# EEZ_DIB_AUX_PS_r2B1.net
KiCad netlist of a schematic drawn in EAGLE
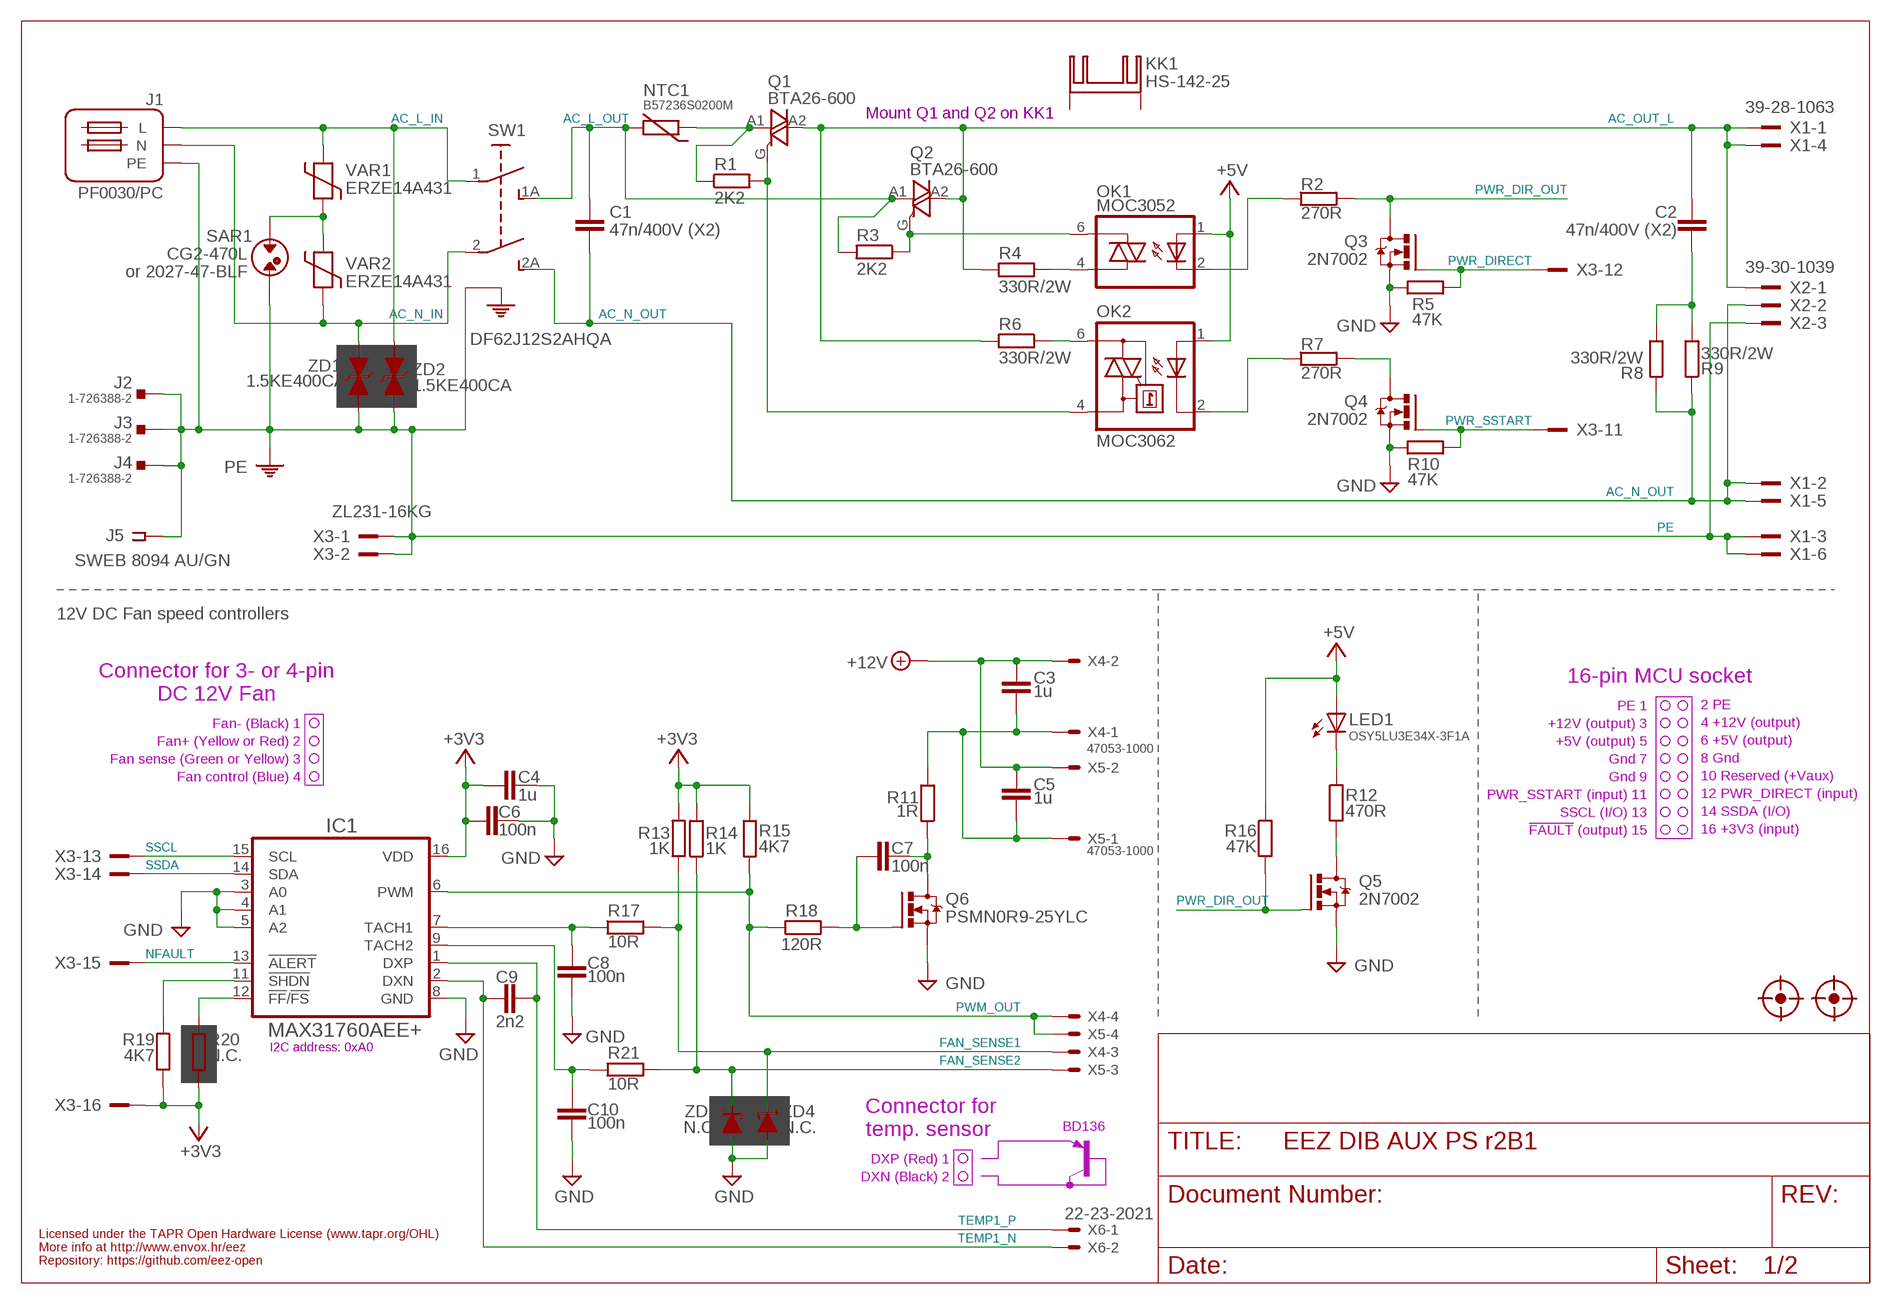
[diagram p0: schematic, sheet 1]
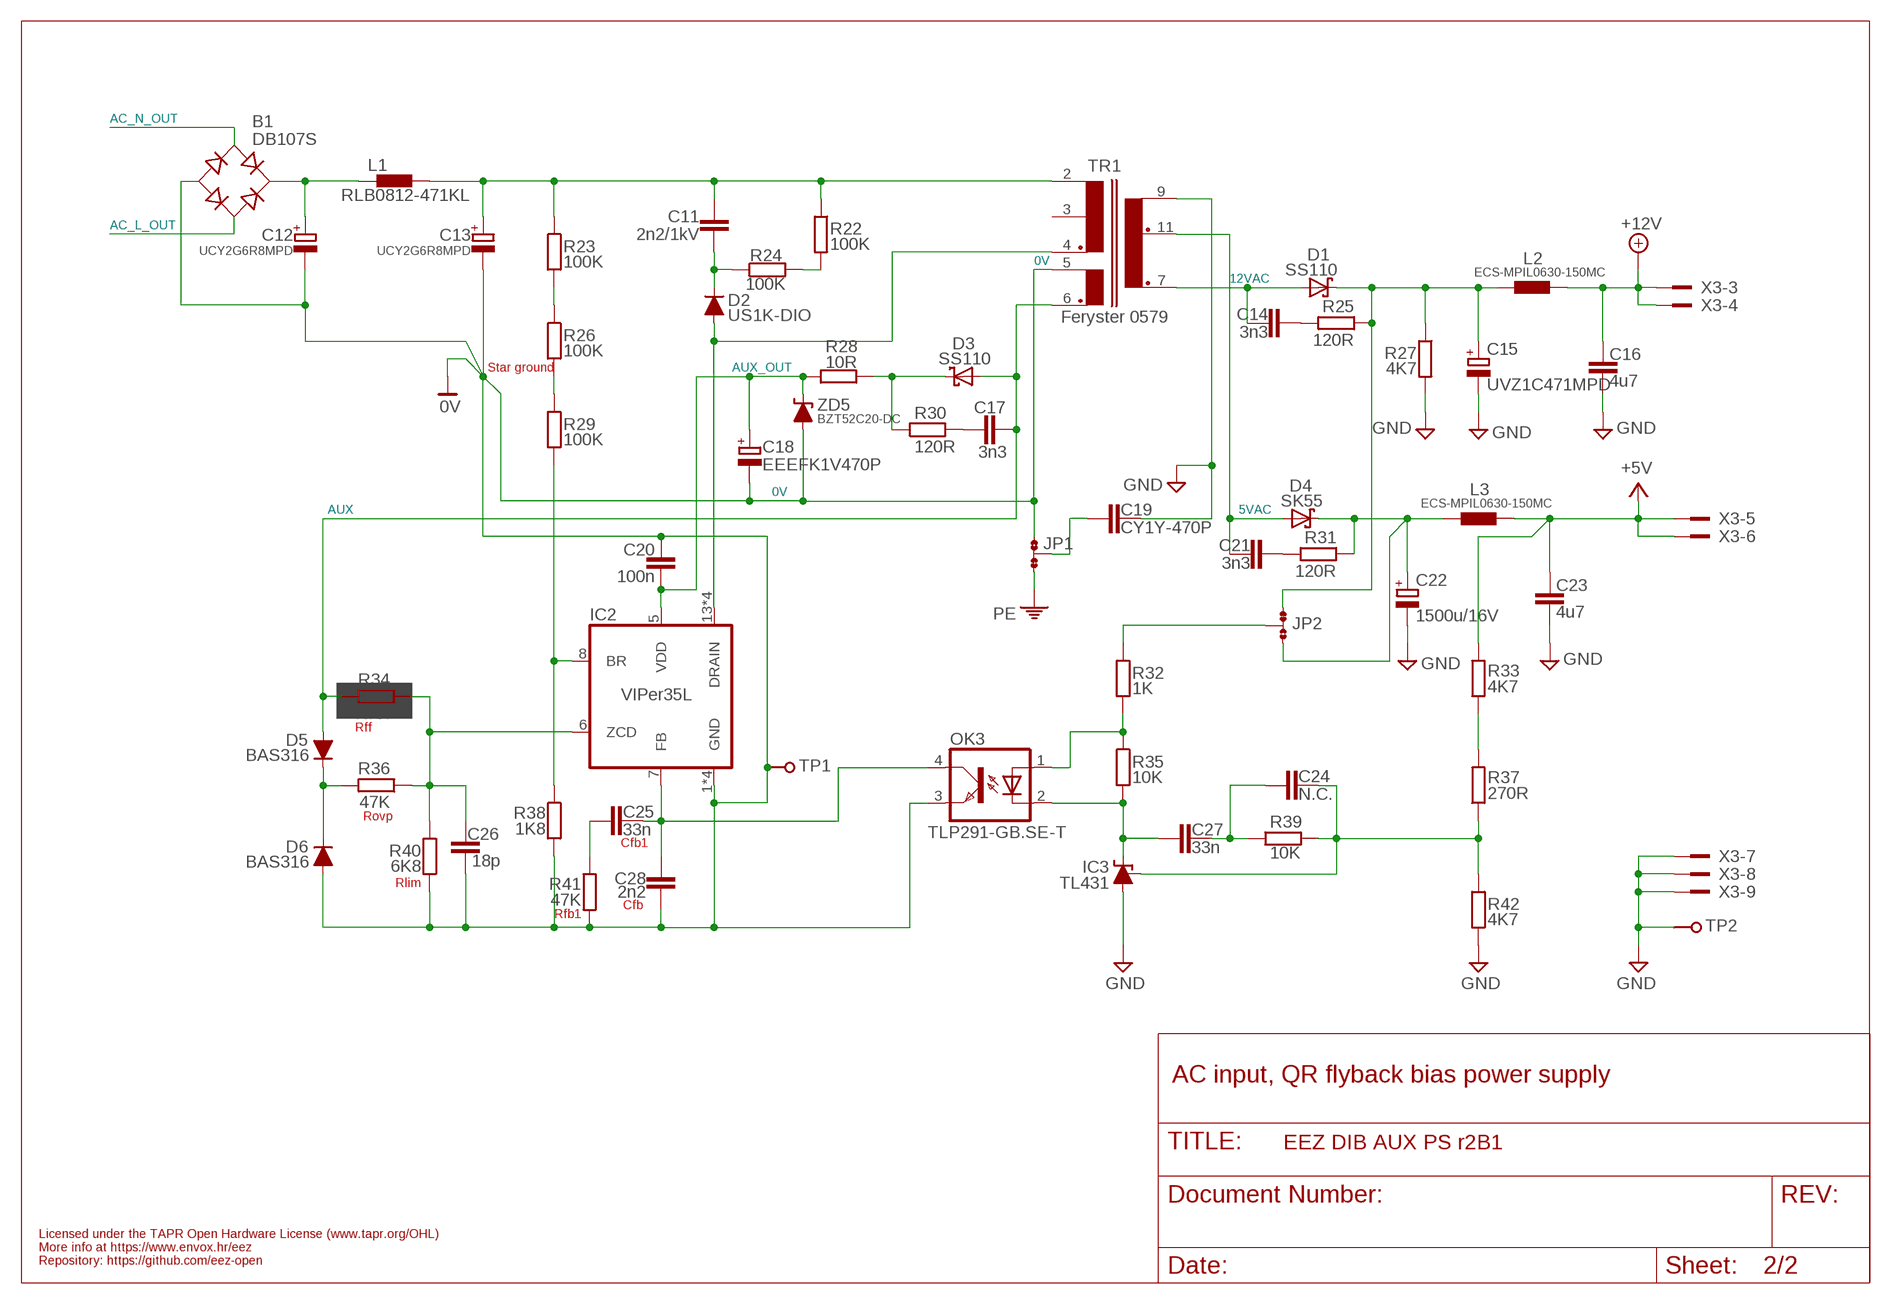
[diagram p1: schematic, sheet 2]

(export (version "E")
  (design (tool "Eeschema 10.0.6"))
  (components
    (comp (ref "B1")
      (value "DB107S")
      (footprint "eagle-import:DBS")
      (libsource (lib "eagle-import") (part "DB?GS107"))
    )
    (comp (ref "C11")
      (value "2n2/1kV")
      (footprint "eagle-import:C1210")
      (libsource (lib "eagle-import") (part "C-EUC1210"))
    )
    (comp (ref "C12")
      (value "UCY2G6R8MPD")
      (footprint "eagle-import:ECAP5_10.5")
      (libsource (lib "eagle-import") (part "ECAP5G_10.5MM"))
    )
    (comp (ref "C13")
      (value "UCY2G6R8MPD")
      (footprint "eagle-import:ECAP5_10.5")
      (libsource (lib "eagle-import") (part "ECAP5G_10.5MM"))
    )
    (comp (ref "C14")
      (value "3n3")
      (footprint "eagle-import:C0805")
      (libsource (lib "eagle-import") (part "C-EUC0805"))
    )
    (comp (ref "C15")
      (value "UVZ1C471MPD")
      (footprint "eagle-import:ECAP3.5_8")
      (libsource (lib "eagle-import") (part "ECAP3.5G_8MM"))
    )
    (comp (ref "C16")
      (value "4u7")
      (footprint "eagle-import:C1210")
      (libsource (lib "eagle-import") (part "C-EUC1210"))
    )
    (comp (ref "C17")
      (value "3n3")
      (footprint "eagle-import:C0805")
      (libsource (lib "eagle-import") (part "C-EUC0805"))
    )
    (comp (ref "C18")
      (value "EEEFK1V470P")
      (footprint "eagle-import:CAPAE660X610N")
      (libsource (lib "eagle-import") (part "ECAPPANASONIC_H"))
    )
    (comp (ref "C19")
      (value "CY1Y-470P")
      (footprint "eagle-import:CY075-032X103")
      (libsource (lib "eagle-import") (part "C-EUCY"))
    )
    (comp (ref "C20")
      (value "100n")
      (footprint "eagle-import:C0603")
      (libsource (lib "eagle-import") (part "C-EUC0603"))
    )
    (comp (ref "C21")
      (value "3n3")
      (footprint "eagle-import:C0805")
      (libsource (lib "eagle-import") (part "C-EUC0805"))
    )
    (comp (ref "C22")
      (value "1500u/16V")
      (footprint "eagle-import:ECAP5_13")
      (libsource (lib "eagle-import") (part "ECAP5G_13MM"))
    )
    (comp (ref "C23")
      (value "4u7")
      (footprint "eagle-import:C1210")
      (libsource (lib "eagle-import") (part "C-EUC1210"))
    )
    (comp (ref "C24")
      (value "N.C.")
      (footprint "eagle-import:C0805")
      (libsource (lib "eagle-import") (part "C-EUC0805"))
    )
    (comp (ref "C25")
      (value "33n")
      (footprint "eagle-import:C0805")
      (libsource (lib "eagle-import") (part "C-EUC0805"))
    )
    (comp (ref "C26")
      (value "18p")
      (footprint "eagle-import:C0603")
      (libsource (lib "eagle-import") (part "C-EUC0603"))
    )
    (comp (ref "C27")
      (value "33n")
      (footprint "eagle-import:C0805")
      (libsource (lib "eagle-import") (part "C-EUC0805"))
    )
    (comp (ref "C28")
      (value "2n2")
      (footprint "eagle-import:C0805")
      (libsource (lib "eagle-import") (part "C-EUC0805"))
    )
    (comp (ref "D1")
      (value "SS110")
      (footprint "eagle-import:SMB")
      (libsource (lib "eagle-import") (part "SCHOTTKYSMB"))
    )
    (comp (ref "D2")
      (value "US1K-DIO")
      (footprint "eagle-import:DO214AA")
      (libsource (lib "eagle-import") (part "DIODEDO214AA"))
    )
    (comp (ref "D3")
      (value "SS110")
      (footprint "eagle-import:SMB")
      (libsource (lib "eagle-import") (part "SCHOTTKYSMB"))
    )
    (comp (ref "D4")
      (value "SK55")
      (footprint "eagle-import:SMB")
      (libsource (lib "eagle-import") (part "SCHOTTKYSMB"))
    )
    (comp (ref "D5")
      (value "BAS316")
      (footprint "eagle-import:SOD323-R")
      (libsource (lib "eagle-import") (part "DIODESOD323R"))
    )
    (comp (ref "D6")
      (value "BAS316")
      (footprint "eagle-import:SOD323-R")
      (libsource (lib "eagle-import") (part "DIODESOD323R"))
    )
    (comp (ref "IC2")
      (value "VIPer35L")
      (footprint "eagle-import:SOIC-16")
      (libsource (lib "eagle-import") (part "VIPER35"))
    )
    (comp (ref "IC3")
      (value "TL431")
      (footprint "eagle-import:SOT103P240X110-3N")
      (libsource (lib "eagle-import") (part "TL431"))
    )
    (comp (ref "JP1")
      (value "JP3-CUT")
      (footprint "eagle-import:JP3-CUT")
      (libsource (lib "eagle-import") (part "JP3-CUT"))
    )
    (comp (ref "JP2")
      (value "JP3-CUT")
      (footprint "eagle-import:JP3-CUT")
      (libsource (lib "eagle-import") (part "JP3-CUT"))
    )
    (comp (ref "L1")
      (value "RLB0812-471KL")
      (footprint "eagle-import:FERSYTER_DSZ6")
      (libsource (lib "eagle-import") (part "FERYSTER_DSZ6"))
    )
    (comp (ref "L2")
      (value "ECS-MPIL0630-150MC")
      (footprint "eagle-import:DE0704")
      (libsource (lib "eagle-import") (part "DE0704"))
    )
    (comp (ref "L3")
      (value "ECS-MPIL0630-150MC")
      (footprint "eagle-import:DE0704")
      (libsource (lib "eagle-import") (part "DE0704"))
    )
    (comp (ref "OK3")
      (value "TLP291-GB.SE-T")
      (footprint "eagle-import:SO4")
      (libsource (lib "eagle-import") (part "TLP291"))
    )
    (comp (ref "R22")
      (value "100K")
      (footprint "eagle-import:R1206")
      (libsource (lib "eagle-import") (part "R-EU_R1206"))
    )
    (comp (ref "R23")
      (value "100K")
      (footprint "eagle-import:R1206")
      (libsource (lib "eagle-import") (part "R-EU_R1206"))
    )
    (comp (ref "R24")
      (value "100K")
      (footprint "eagle-import:R1206")
      (libsource (lib "eagle-import") (part "R-EU_R1206"))
    )
    (comp (ref "R25")
      (value "120R")
      (footprint "eagle-import:R0805")
      (libsource (lib "eagle-import") (part "R-EU_R0805"))
    )
    (comp (ref "R26")
      (value "100K")
      (footprint "eagle-import:R1206")
      (libsource (lib "eagle-import") (part "R-EU_R1206"))
    )
    (comp (ref "R27")
      (value "4K7")
      (footprint "eagle-import:R0805")
      (libsource (lib "eagle-import") (part "R-EU_R0805"))
    )
    (comp (ref "R28")
      (value "10R")
      (footprint "eagle-import:R0805")
      (libsource (lib "eagle-import") (part "R-EU_R0805"))
    )
    (comp (ref "R29")
      (value "100K")
      (footprint "eagle-import:R1206")
      (libsource (lib "eagle-import") (part "R-EU_R1206"))
    )
    (comp (ref "R30")
      (value "120R")
      (footprint "eagle-import:R0805")
      (libsource (lib "eagle-import") (part "R-EU_R0805"))
    )
    (comp (ref "R31")
      (value "120R")
      (footprint "eagle-import:R0805")
      (libsource (lib "eagle-import") (part "R-EU_R0805"))
    )
    (comp (ref "R32")
      (value "1K")
      (footprint "eagle-import:R0805")
      (libsource (lib "eagle-import") (part "R-EU_R0805"))
    )
    (comp (ref "R33")
      (value "4K7")
      (footprint "eagle-import:R0805")
      (libsource (lib "eagle-import") (part "R-EU_R0805"))
    )
    (comp (ref "R34")
      (value "N.C.")
      (footprint "eagle-import:R0805")
      (libsource (lib "eagle-import") (part "R-EU_R0805"))
    )
    (comp (ref "R35")
      (value "10K")
      (footprint "eagle-import:R0805")
      (libsource (lib "eagle-import") (part "R-EU_R0805"))
    )
    (comp (ref "R36")
      (value "47K")
      (footprint "eagle-import:R0805")
      (libsource (lib "eagle-import") (part "R-EU_R0805"))
    )
    (comp (ref "R37")
      (value "270R")
      (footprint "eagle-import:R0805")
      (libsource (lib "eagle-import") (part "R-EU_R0805"))
    )
    (comp (ref "R38")
      (value "1K8")
      (footprint "eagle-import:R0805")
      (libsource (lib "eagle-import") (part "R-EU_R0805"))
    )
    (comp (ref "R39")
      (value "10K")
      (footprint "eagle-import:R0805")
      (libsource (lib "eagle-import") (part "R-EU_R0805"))
    )
    (comp (ref "R40")
      (value "6K8")
      (footprint "eagle-import:R0805")
      (libsource (lib "eagle-import") (part "R-EU_R0805"))
    )
    (comp (ref "R41")
      (value "47K")
      (footprint "eagle-import:R0805")
      (libsource (lib "eagle-import") (part "R-EU_R0805"))
    )
    (comp (ref "R42")
      (value "4K7")
      (footprint "eagle-import:R0805")
      (libsource (lib "eagle-import") (part "R-EU_R0805"))
    )
    (comp (ref "TP1")
      (value "PCB_TEST_TABSHIELD")
      (footprint "eagle-import:PCB_SHIELD_TAB")
      (libsource (lib "eagle-import") (part "PCB_TEST_TABSHIELD"))
    )
    (comp (ref "TP2")
      (value "PCB_TEST_TABSHIELD")
      (footprint "eagle-import:PCB_SHIELD_TAB")
      (libsource (lib "eagle-import") (part "PCB_TEST_TABSHIELD"))
    )
    (comp (ref "TR1")
      (value "Feryster 0579")
      (footprint "eagle-import:FERYSTER_0579")
      (libsource (lib "eagle-import") (part "FERYSTER_0579"))
    )
    (comp (ref "X3")
      (value "ZL231-16KG")
      (footprint "eagle-import:ML16L")
      (libsource (lib "eagle-import") (part "IDC-16PIN-ANGLED"))
    )
    (comp (ref "ZD5")
      (value "BZT52C20-DC")
      (footprint "eagle-import:SOD123")
      (libsource (lib "eagle-import") (part "ZENER-DIODESOD123"))
    )
    (comp (ref "C1")
      (value "47n/400V (X2)")
      (footprint "eagle-import:C102-054X133")
      (libsource (lib "eagle-import") (part "C-EU102-054X133"))
    )
    (comp (ref "C2")
      (value "47n/400V (X2)")
      (footprint "eagle-import:C102-054X133")
      (libsource (lib "eagle-import") (part "C-EU102-054X133"))
    )
    (comp (ref "C3")
      (value "1u")
      (footprint "eagle-import:C0805")
      (libsource (lib "eagle-import") (part "C-EUC0805"))
    )
    (comp (ref "C4")
      (value "1u")
      (footprint "eagle-import:C0805")
      (libsource (lib "eagle-import") (part "C-EUC0805"))
    )
    (comp (ref "C5")
      (value "1u")
      (footprint "eagle-import:C0805")
      (libsource (lib "eagle-import") (part "C-EUC0805"))
    )
    (comp (ref "C6")
      (value "100n")
      (footprint "eagle-import:C0603")
      (libsource (lib "eagle-import") (part "C-EUC0603"))
    )
    (comp (ref "C7")
      (value "100n")
      (footprint "eagle-import:C0805")
      (libsource (lib "eagle-import") (part "C-EUC0805"))
    )
    (comp (ref "C8")
      (value "100n")
      (footprint "eagle-import:C0603")
      (libsource (lib "eagle-import") (part "C-EUC0603"))
    )
    (comp (ref "C9")
      (value "2n2")
      (footprint "eagle-import:C0805")
      (libsource (lib "eagle-import") (part "C-EUC0805"))
    )
    (comp (ref "C10")
      (value "100n")
      (footprint "eagle-import:C0603")
      (libsource (lib "eagle-import") (part "C-EUC0603"))
    )
    (comp (ref "FM1")
      (value "FIDUCIAL")
      (footprint "eagle-import:FIDUCIAL")
      (libsource (lib "eagle-import") (part "FIDUCIAL"))
    )
    (comp (ref "FM2")
      (value "FIDUCIAL")
      (footprint "eagle-import:FIDUCIAL")
      (libsource (lib "eagle-import") (part "FIDUCIAL"))
    )
    (comp (ref "IC1")
      (value "MAX31760AEE+")
      (footprint "eagle-import:DBQ16")
      (libsource (lib "eagle-import") (part "MAX31760AEE+"))
    )
    (comp (ref "J1")
      (value "PF0030/PC")
      (footprint "eagle-import:PF0030_PC")
      (libsource (lib "eagle-import") (part "PF0030/PC"))
    )
    (comp (ref "J2")
      (value "1-726388-2")
      (footprint "eagle-import:PCB_TAB-4.8MM")
      (libsource (lib "eagle-import") (part "PCB_TAB4.8MM"))
    )
    (comp (ref "J3")
      (value "1-726388-2")
      (footprint "eagle-import:PCB_TAB-4.8MM")
      (libsource (lib "eagle-import") (part "PCB_TAB4.8MM"))
    )
    (comp (ref "J4")
      (value "1-726388-2")
      (footprint "eagle-import:PCB_TAB-4.8MM")
      (libsource (lib "eagle-import") (part "PCB_TAB4.8MM"))
    )
    (comp (ref "J5")
      (value "SWEB 8094 AU/GN")
      (footprint "eagle-import:S16N-PC")
      (libsource (lib "eagle-import") (part "BINDING_POSTCLIFF"))
    )
    (comp (ref "KK1")
      (value "HS-142-25")
      (footprint "eagle-import:SK129")
      (libsource (lib "eagle-import") (part "SK129-PAD"))
    )
    (comp (ref "LED1")
      (value "OSY5LU3E34X-3F1A")
      (footprint "eagle-import:OSG8")
      (libsource (lib "eagle-import") (part "LEDOSG8"))
    )
    (comp (ref "NTC1")
      (value "B57236S0200M")
      (footprint "eagle-import:NTC_11.5X6_RM5")
      (libsource (lib "eagle-import") (part "NTC11.5X6"))
    )
    (comp (ref "OK1")
      (value "MOC3052")
      (footprint "eagle-import:DIL6-SMD")
      (libsource (lib "eagle-import") (part "MOC305X"))
    )
    (comp (ref "OK2")
      (value "MOC3062")
      (footprint "eagle-import:DIL6-SMD")
      (fields
        (field (name "MF") "FAIRCHILD SEMICONDUCTOR")
        (field (name "MPN") "MOC3033S-M")
        (field (name "MF_1") "FAIRCHILD SEMICONDUCTOR")
        (field (name "MPN_1") "MOC3033S-M")
        (field (name "OC_FARNELL") "unknown")
        (field (name "OC_NEWARK") "05C2878")
      )
      (libsource (lib "eagle-import") (part "MOC30S33"))
    )
    (comp (ref "Q1")
      (value "BTA26-600")
      (footprint "eagle-import:TOP3S-1")
      (libsource (lib "eagle-import") (part "BTA26-V"))
    )
    (comp (ref "Q2")
      (value "BTA26-600")
      (footprint "eagle-import:TOP3S-1")
      (libsource (lib "eagle-import") (part "BTA26-V"))
    )
    (comp (ref "Q3")
      (value "2N7002")
      (footprint "eagle-import:SOT103P240X110-3N")
      (fields (field (name "MPN") "2N7002-7-F"))
      (libsource (lib "eagle-import") (part "2N7002"))
    )
    (comp (ref "Q4")
      (value "2N7002")
      (footprint "eagle-import:SOT103P240X110-3N")
      (fields (field (name "MPN") "2N7002-7-F"))
      (libsource (lib "eagle-import") (part "2N7002"))
    )
    (comp (ref "Q5")
      (value "2N7002")
      (footprint "eagle-import:SOT103P240X110-3N")
      (fields
        (field (name "MPN") "2N7002-7-F")
        (field (name "MPN_1") "2N7002-7-F")
        (field (name "OC_FARNELL") "1713823")
        (field (name "OC_NEWARK") "25R5679")
        (field (name "PACKAGE") "SOT-23-3")
        (field (name "SUPPLIER") "DIODES INC.")
      )
      (libsource (lib "eagle-import") (part "2N7002"))
    )
    (comp (ref "Q6")
      (value "PSMN0R9-25YLC")
      (footprint "eagle-import:SOT669")
      (libsource (lib "eagle-import") (part "N-MOSFETLFPAK"))
    )
    (comp (ref "R1")
      (value "2K2")
      (footprint "eagle-import:R0805")
      (libsource (lib "eagle-import") (part "R-EU_R0805"))
    )
    (comp (ref "R2")
      (value "270R")
      (footprint "eagle-import:R0805")
      (libsource (lib "eagle-import") (part "R-EU_R0805"))
    )
    (comp (ref "R3")
      (value "2K2")
      (footprint "eagle-import:R0805")
      (libsource (lib "eagle-import") (part "R-EU_R0805"))
    )
    (comp (ref "R4")
      (value "330R/2W")
      (footprint "eagle-import:R2512")
      (libsource (lib "eagle-import") (part "R-EU_R2512"))
    )
    (comp (ref "R5")
      (value "47K")
      (footprint "eagle-import:R0805")
      (libsource (lib "eagle-import") (part "R-EU_R0805"))
    )
    (comp (ref "R6")
      (value "330R/2W")
      (footprint "eagle-import:R2512")
      (libsource (lib "eagle-import") (part "R-EU_R2512"))
    )
    (comp (ref "R7")
      (value "270R")
      (footprint "eagle-import:R0805")
      (libsource (lib "eagle-import") (part "R-EU_R0805"))
    )
    (comp (ref "R8")
      (value "330R/2W")
      (footprint "eagle-import:R2512")
      (libsource (lib "eagle-import") (part "R-EU_R2512"))
    )
    (comp (ref "R9")
      (value "330R/2W")
      (footprint "eagle-import:R2512")
      (libsource (lib "eagle-import") (part "R-EU_R2512"))
    )
    (comp (ref "R10")
      (value "47K")
      (footprint "eagle-import:R0805")
      (libsource (lib "eagle-import") (part "R-EU_R0805"))
    )
    (comp (ref "R11")
      (value "1R")
      (footprint "eagle-import:R0805")
      (libsource (lib "eagle-import") (part "R-EU_R0805"))
    )
    (comp (ref "R12")
      (value "470R")
      (footprint "eagle-import:R0805")
      (libsource (lib "eagle-import") (part "R-EU_R0805"))
    )
    (comp (ref "R13")
      (value "1K")
      (footprint "eagle-import:R0805")
      (libsource (lib "eagle-import") (part "R-EU_R0805"))
    )
    (comp (ref "R14")
      (value "1K")
      (footprint "eagle-import:R0805")
      (libsource (lib "eagle-import") (part "R-EU_R0805"))
    )
    (comp (ref "R15")
      (value "4K7")
      (footprint "eagle-import:R0805")
      (libsource (lib "eagle-import") (part "R-EU_R0805"))
    )
    (comp (ref "R16")
      (value "47K")
      (footprint "eagle-import:R0805")
      (libsource (lib "eagle-import") (part "R-EU_R0805"))
    )
    (comp (ref "R17")
      (value "10R")
      (footprint "eagle-import:R0805")
      (libsource (lib "eagle-import") (part "R-EU_R0805"))
    )
    (comp (ref "R18")
      (value "120R")
      (footprint "eagle-import:R0805")
      (libsource (lib "eagle-import") (part "R-EU_R0805"))
    )
    (comp (ref "R19")
      (value "4K7")
      (footprint "eagle-import:R0805")
      (libsource (lib "eagle-import") (part "R-EU_R0805"))
    )
    (comp (ref "R20")
      (value "N.C.")
      (footprint "eagle-import:R0805")
      (libsource (lib "eagle-import") (part "R-EU_R0805"))
    )
    (comp (ref "R21")
      (value "10R")
      (footprint "eagle-import:R0805")
      (libsource (lib "eagle-import") (part "R-EU_R0805"))
    )
    (comp (ref "SAR1")
      (value "CG2-470L")
      (footprint "eagle-import:SAR")
      (libsource (lib "eagle-import") (part "SAR"))
    )
    (comp (ref "SW1")
      (value "DF62J12S2AHQA")
      (footprint "eagle-import:DF62J12S2")
      (libsource (lib "eagle-import") (part "DF62J12S2AHQA"))
    )
    (comp (ref "VAR1")
      (value "ERZE14A431")
      (footprint "eagle-import:VARISTOR_13MM")
      (libsource (lib "eagle-import") (part "VARISTOR-13"))
    )
    (comp (ref "VAR2")
      (value "ERZE14A431")
      (footprint "eagle-import:VARISTOR_13MM")
      (libsource (lib "eagle-import") (part "VARISTOR-13"))
    )
    (comp (ref "X1")
      (value "39-28-1063")
      (footprint "eagle-import:MINIFIT_5566-06A_CRE")
      (libsource (lib "eagle-import") (part "MINIFIT_5566-06A-CRE"))
    )
    (comp (ref "X2")
      (value "39-30-1039")
      (footprint "eagle-import:MINIFIT_39301039_CRE")
      (libsource (lib "eagle-import") (part "MINIFIT_39301039-CREEPAGE"))
    )
    (comp (ref "X4")
      (value "47053-1000")
      (footprint "eagle-import:47053-1000")
      (libsource (lib "eagle-import") (part "47053-1000"))
    )
    (comp (ref "X5")
      (value "47053-1000")
      (footprint "eagle-import:47053-1000")
      (libsource (lib "eagle-import") (part "47053-1000"))
    )
    (comp (ref "X6")
      (value "22-23-2021")
      (footprint "eagle-import:22-23-2021")
      (fields (field (name "MF") "MOLEX"))
      (libsource (lib "eagle-import") (part "22-23-2021"))
    )
    (comp (ref "ZD1")
      (value "1.5KE400CA")
      (footprint "eagle-import:DO201-BIDIR")
      (libsource (lib "eagle-import") (part "1.5KE-BIDIR"))
    )
    (comp (ref "ZD2")
      (value "1.5KE400CA")
      (footprint "eagle-import:DO201-BIDIR")
      (libsource (lib "eagle-import") (part "1.5KE-BIDIR"))
    )
    (comp (ref "ZD3")
      (value "N.C.")
      (footprint "eagle-import:SOD123")
      (libsource (lib "eagle-import") (part "ZENER-DIODESOD123"))
    )
    (comp (ref "ZD4")
      (value "N.C.")
      (footprint "eagle-import:SOD123")
      (libsource (lib "eagle-import") (part "ZENER-DIODESOD123"))
    )
  )
  (nets
    (net (code "1") (name "+3V3") (class "Default")
      (node (ref "C4") (pin "2") (pinfunction "2_2") (pintype "passive"))
      (node (ref "C6") (pin "2") (pinfunction "2_2") (pintype "passive"))
      (node (ref "IC1") (pin "16") (pinfunction "VDD_16") (pintype "power_in"))
      (node (ref "R13") (pin "2") (pinfunction "2_2") (pintype "passive"))
      (node (ref "R14") (pin "2") (pinfunction "2_2") (pintype "passive"))
      (node (ref "R15") (pin "1") (pinfunction "1_1") (pintype "passive"))
      (node (ref "R19") (pin "2") (pinfunction "2_2") (pintype "passive"))
      (node (ref "R20") (pin "2") (pinfunction "2_2") (pintype "passive"))
      (node (ref "X3") (pin "16") (pinfunction "1_16") (pintype "passive"))
    )
    (net (code "2") (name "+5V") (class "Default")
      (node (ref "C23") (pin "1") (pinfunction "1_1") (pintype "passive"))
      (node (ref "L3") (pin "2") (pinfunction "2_2") (pintype "passive"))
      (node (ref "LED1") (pin "A") (pinfunction "A_A") (pintype "passive"))
      (node (ref "OK1") (pin "1") (pinfunction "A_1") (pintype "passive"))
      (node (ref "OK2") (pin "1") (pinfunction "A_1") (pintype "passive"))
      (node (ref "R16") (pin "1") (pinfunction "1_1") (pintype "passive"))
      (node (ref "R33") (pin "2") (pinfunction "2_2") (pintype "passive"))
      (node (ref "X3") (pin "5") (pinfunction "1_5") (pintype "passive"))
      (node (ref "X3") (pin "6") (pinfunction "1_6") (pintype "passive"))
    )
    (net (code "3") (name "+12V") (class "Default")
      (node (ref "C16") (pin "1") (pinfunction "1_1") (pintype "passive"))
      (node (ref "C3") (pin "1") (pinfunction "1_1") (pintype "passive"))
      (node (ref "C5") (pin "1") (pinfunction "1_1") (pintype "passive"))
      (node (ref "L2") (pin "2") (pinfunction "2_2") (pintype "passive"))
      (node (ref "X3") (pin "3") (pinfunction "1_3") (pintype "passive"))
      (node (ref "X3") (pin "4") (pinfunction "1_4") (pintype "passive"))
      (node (ref "X4") (pin "2") (pinfunction "S_2") (pintype "passive"))
      (node (ref "X5") (pin "2") (pinfunction "S_2") (pintype "passive"))
    )
    (net (code "4") (name "0V") (class "Default")
      (node (ref "B1") (pin "-") (pinfunction "-_-") (pintype "passive"))
      (node (ref "C12") (pin "-") (pinfunction "-_-") (pintype "passive"))
      (node (ref "C13") (pin "-") (pinfunction "-_-") (pintype "passive"))
      (node (ref "C18") (pin "2") (pinfunction "-_2") (pintype "passive"))
      (node (ref "C20") (pin "1") (pinfunction "1_1") (pintype "passive"))
      (node (ref "C26") (pin "2") (pinfunction "2_2") (pintype "passive"))
      (node (ref "C28") (pin "2") (pinfunction "2_2") (pintype "passive"))
      (node (ref "D6") (pin "A") (pinfunction "A_A") (pintype "passive"))
      (node (ref "IC2") (pin "1") (pinfunction "GND_1") (pintype "passive"))
      (node (ref "IC2") (pin "2") (pinfunction "GND_2") (pintype "passive"))
      (node (ref "IC2") (pin "3") (pinfunction "GND_3") (pintype "passive"))
      (node (ref "IC2") (pin "4") (pinfunction "GND_4") (pintype "passive"))
      (node (ref "JP1") (pin "NO") (pinfunction "NO_NO") (pintype "passive"))
      (node (ref "OK3") (pin "3") (pinfunction "EMIT_3") (pintype "passive"))
      (node (ref "R38") (pin "2") (pinfunction "2_2") (pintype "passive"))
      (node (ref "R40") (pin "1") (pinfunction "1_1") (pintype "passive"))
      (node (ref "R41") (pin "2") (pinfunction "2_2") (pintype "passive"))
      (node (ref "TP1") (pin "1") (pinfunction "P$1_1") (pintype "bidirectional"))
      (node (ref "TR1") (pin "5") (pinfunction "AUX_5") (pintype "passive"))
      (node (ref "ZD5") (pin "A") (pinfunction "A_A") (pintype "passive"))
    )
    (net (code "5") (name "5VAC") (class "Default")
      (node (ref "C21") (pin "2") (pinfunction "2_2") (pintype "passive"))
      (node (ref "D4") (pin "A") (pinfunction "A_A") (pintype "passive"))
      (node (ref "TR1") (pin "11") (pinfunction "S1_DOT_11") (pintype "passive"))
    )
    (net (code "6") (name "12VAC") (class "Default")
      (node (ref "C14") (pin "2") (pinfunction "2_2") (pintype "passive"))
      (node (ref "D1") (pin "A") (pinfunction "A_A") (pintype "passive"))
      (node (ref "TR1") (pin "7") (pinfunction "S2_DOT_7") (pintype "passive"))
    )
    (net (code "7") (name "AC_L_IN") (class "Default")
      (node (ref "J1") (pin "L") (pinfunction "L_L") (pintype "bidirectional"))
      (node (ref "SW1") (pin "1") (pinfunction "P_1") (pintype "passive"))
      (node (ref "VAR1") (pin "2") (pinfunction "P$2_2") (pintype "bidirectional"))
      (node (ref "ZD2") (pin "A") (pinfunction "2_A") (pintype "passive"))
    )
    (net (code "8") (name "AC_L_OUT") (class "Default")
      (node (ref "B1") (pin "AC2") (pinfunction "AC2_AC2") (pintype "passive"))
      (node (ref "C1") (pin "1") (pinfunction "1_1") (pintype "passive"))
      (node (ref "NTC1") (pin "1") (pinfunction "P$1_1") (pintype "bidirectional"))
      (node (ref "Q2") (pin "A1") (pinfunction "A1_A1") (pintype "passive"))
      (node (ref "R3") (pin "2") (pinfunction "2_2") (pintype "passive"))
      (node (ref "SW1") (pin "1A") (pinfunction "S_1A") (pintype "passive"))
    )
    (net (code "9") (name "AC_N_IN") (class "Default")
      (node (ref "J1") (pin "N") (pinfunction "N_N") (pintype "bidirectional"))
      (node (ref "SW1") (pin "2") (pinfunction "P1_2") (pintype "passive"))
      (node (ref "VAR2") (pin "1") (pinfunction "P$1_1") (pintype "bidirectional"))
      (node (ref "ZD1") (pin "A") (pinfunction "2_A") (pintype "passive"))
    )
    (net (code "10") (name "AC_N_OUT") (class "Default")
      (node (ref "B1") (pin "AC1") (pinfunction "AC1_AC1") (pintype "passive"))
      (node (ref "C1") (pin "2") (pinfunction "2_2") (pintype "passive"))
      (node (ref "R8") (pin "1") (pinfunction "1_1") (pintype "passive"))
      (node (ref "R9") (pin "1") (pinfunction "1_1") (pintype "passive"))
      (node (ref "SW1") (pin "2A") (pinfunction "S1_2A") (pintype "passive"))
      (node (ref "X1") (pin "2") (pinfunction "1_2") (pintype "passive"))
      (node (ref "X1") (pin "5") (pinfunction "1_5") (pintype "passive"))
      (node (ref "X2") (pin "2") (pinfunction "1_2") (pintype "passive"))
    )
    (net (code "11") (name "AC_OUT_L") (class "Default")
      (node (ref "C2") (pin "1") (pinfunction "1_1") (pintype "passive"))
      (node (ref "Q1") (pin "A2") (pinfunction "A2_A2") (pintype "passive"))
      (node (ref "Q2") (pin "A2") (pinfunction "A2_A2") (pintype "passive"))
      (node (ref "R4") (pin "2") (pinfunction "2_2") (pintype "passive"))
      (node (ref "R6") (pin "2") (pinfunction "2_2") (pintype "passive"))
      (node (ref "X1") (pin "1") (pinfunction "1_1") (pintype "passive"))
      (node (ref "X1") (pin "4") (pinfunction "1_4") (pintype "passive"))
      (node (ref "X2") (pin "1") (pinfunction "1_1") (pintype "passive"))
    )
    (net (code "12") (name "AUX") (class "Default")
      (node (ref "C17") (pin "2") (pinfunction "2_2") (pintype "passive"))
      (node (ref "D3") (pin "A") (pinfunction "A_A") (pintype "passive"))
      (node (ref "D5") (pin "A") (pinfunction "A_A") (pintype "passive"))
      (node (ref "R34") (pin "2") (pinfunction "2_2") (pintype "passive"))
      (node (ref "TR1") (pin "6") (pinfunction "AUX_DOT_6") (pintype "passive"))
    )
    (net (code "13") (name "AUX_OUT") (class "Default")
      (node (ref "C18") (pin "1") (pinfunction "+_1") (pintype "passive"))
      (node (ref "C20") (pin "2") (pinfunction "2_2") (pintype "passive"))
      (node (ref "IC2") (pin "5") (pinfunction "VDD_5") (pintype "power_in"))
      (node (ref "R28") (pin "2") (pinfunction "2_2") (pintype "passive"))
      (node (ref "ZD5") (pin "C") (pinfunction "C_C") (pintype "passive"))
    )
    (net (code "14") (name "FAN_SENSE1") (class "Default")
      (node (ref "R13") (pin "1") (pinfunction "1_1") (pintype "passive"))
      (node (ref "R17") (pin "2") (pinfunction "2_2") (pintype "passive"))
      (node (ref "X4") (pin "3") (pinfunction "S_3") (pintype "passive"))
      (node (ref "ZD4") (pin "C") (pinfunction "C_C") (pintype "passive"))
    )
    (net (code "15") (name "FAN_SENSE2") (class "Default")
      (node (ref "R14") (pin "1") (pinfunction "1_1") (pintype "passive"))
      (node (ref "R21") (pin "2") (pinfunction "2_2") (pintype "passive"))
      (node (ref "X5") (pin "3") (pinfunction "S_3") (pintype "passive"))
      (node (ref "ZD3") (pin "C") (pinfunction "C_C") (pintype "passive"))
    )
    (net (code "16") (name "GND") (class "Default")
      (node (ref "C10") (pin "2") (pinfunction "2_2") (pintype "passive"))
      (node (ref "C15") (pin "-") (pinfunction "-_-") (pintype "passive"))
      (node (ref "C16") (pin "2") (pinfunction "2_2") (pintype "passive"))
      (node (ref "C19") (pin "2") (pinfunction "2_2") (pintype "passive"))
      (node (ref "C22") (pin "-") (pinfunction "-_-") (pintype "passive"))
      (node (ref "C23") (pin "2") (pinfunction "2_2") (pintype "passive"))
      (node (ref "C4") (pin "1") (pinfunction "1_1") (pintype "passive"))
      (node (ref "C6") (pin "1") (pinfunction "1_1") (pintype "passive"))
      (node (ref "C8") (pin "2") (pinfunction "2_2") (pintype "passive"))
      (node (ref "IC1") (pin "3") (pinfunction "A0_3") (pintype "input"))
      (node (ref "IC1") (pin "4") (pinfunction "A1_4") (pintype "input"))
      (node (ref "IC1") (pin "5") (pinfunction "A2_5") (pintype "input"))
      (node (ref "IC1") (pin "8") (pinfunction "GND_8") (pintype "power_in"))
      (node (ref "IC3") (pin "3") (pinfunction "A_3") (pintype "passive"))
      (node (ref "Q3") (pin "2") (pinfunction "S_2") (pintype "passive"))
      (node (ref "Q4") (pin "2") (pinfunction "S_2") (pintype "passive"))
      (node (ref "Q5") (pin "2") (pinfunction "S_2") (pintype "passive"))
      (node (ref "Q6") (pin "1") (pinfunction "S_1") (pintype "passive"))
      (node (ref "Q6") (pin "2") (pinfunction "S_2") (pintype "passive"))
      (node (ref "Q6") (pin "3") (pinfunction "S_3") (pintype "passive"))
      (node (ref "R10") (pin "1") (pinfunction "1_1") (pintype "passive"))
      (node (ref "R27") (pin "2") (pinfunction "2_2") (pintype "passive"))
      (node (ref "R42") (pin "1") (pinfunction "1_1") (pintype "passive"))
      (node (ref "R5") (pin "1") (pinfunction "1_1") (pintype "passive"))
      (node (ref "TP2") (pin "1") (pinfunction "P$1_1") (pintype "bidirectional"))
      (node (ref "TR1") (pin "9") (pinfunction "S_COMM_9") (pintype "passive"))
      (node (ref "X3") (pin "7") (pinfunction "1_7") (pintype "passive"))
      (node (ref "X3") (pin "8") (pinfunction "1_8") (pintype "passive"))
      (node (ref "X3") (pin "9") (pinfunction "1_9") (pintype "passive"))
      (node (ref "ZD3") (pin "A") (pinfunction "A_A") (pintype "passive"))
      (node (ref "ZD4") (pin "A") (pinfunction "A_A") (pintype "passive"))
    )
    (net (code "17") (name "NFAULT") (class "Default")
      (node (ref "IC1") (pin "13") (pinfunction "~{ALERT}_13") (pintype "output"))
      (node (ref "X3") (pin "15") (pinfunction "1_15") (pintype "passive"))
    )
    (net (code "18") (name "Net-(C2-Pad2)") (class "Default")
      (node (ref "C2") (pin "2") (pinfunction "2_2") (pintype "passive"))
      (node (ref "R8") (pin "2") (pinfunction "2_2") (pintype "passive"))
      (node (ref "R9") (pin "2") (pinfunction "2_2") (pintype "passive"))
    )
    (net (code "19") (name "Net-(C11-Pad2)") (class "Default")
      (node (ref "C11") (pin "2") (pinfunction "2_2") (pintype "passive"))
      (node (ref "D2") (pin "C") (pinfunction "C_C") (pintype "passive"))
      (node (ref "R24") (pin "1") (pinfunction "1_1") (pintype "passive"))
    )
    (net (code "20") (name "Net-(C14-Pad1)") (class "Default")
      (node (ref "C14") (pin "1") (pinfunction "1_1") (pintype "passive"))
      (node (ref "R25") (pin "2") (pinfunction "2_2") (pintype "passive"))
    )
    (net (code "21") (name "Net-(C15-Pad+)") (class "Default")
      (node (ref "C15") (pin "+") (pinfunction "+_+") (pintype "passive"))
      (node (ref "D1") (pin "C") (pinfunction "C_C") (pintype "passive"))
      (node (ref "JP2") (pin "NC") (pinfunction "NC_NC") (pintype "passive"))
      (node (ref "L2") (pin "1") (pinfunction "1_1") (pintype "passive"))
      (node (ref "R25") (pin "1") (pinfunction "1_1") (pintype "passive"))
      (node (ref "R27") (pin "1") (pinfunction "1_1") (pintype "passive"))
    )
    (net (code "22") (name "Net-(C17-Pad1)") (class "Default")
      (node (ref "C17") (pin "1") (pinfunction "1_1") (pintype "passive"))
      (node (ref "R30") (pin "2") (pinfunction "2_2") (pintype "passive"))
    )
    (net (code "23") (name "Net-(C19-Pad1)") (class "Default")
      (node (ref "C19") (pin "1") (pinfunction "1_1") (pintype "passive"))
      (node (ref "JP1") (pin "COM") (pinfunction "COM_COM") (pintype "passive"))
    )
    (net (code "24") (name "Net-(C21-Pad1)") (class "Default")
      (node (ref "C21") (pin "1") (pinfunction "1_1") (pintype "passive"))
      (node (ref "R31") (pin "2") (pinfunction "2_2") (pintype "passive"))
    )
    (net (code "25") (name "Net-(C22-Pad+)") (class "Default")
      (node (ref "C22") (pin "+") (pinfunction "+_+") (pintype "passive"))
      (node (ref "D4") (pin "C") (pinfunction "C_C") (pintype "passive"))
      (node (ref "JP2") (pin "NO") (pinfunction "NO_NO") (pintype "passive"))
      (node (ref "L3") (pin "1") (pinfunction "1_1") (pintype "passive"))
      (node (ref "R31") (pin "1") (pinfunction "1_1") (pintype "passive"))
    )
    (net (code "26") (name "Net-(C24-Pad1)") (class "Default")
      (node (ref "C24") (pin "1") (pinfunction "1_1") (pintype "passive"))
      (node (ref "C27") (pin "2") (pinfunction "2_2") (pintype "passive"))
      (node (ref "R39") (pin "1") (pinfunction "1_1") (pintype "passive"))
    )
    (net (code "27") (name "Net-(C25-Pad1)") (class "Default")
      (node (ref "C25") (pin "1") (pinfunction "1_1") (pintype "passive"))
      (node (ref "R41") (pin "1") (pinfunction "1_1") (pintype "passive"))
    )
    (net (code "28") (name "Net-(D3-PadC)") (class "Default")
      (node (ref "D3") (pin "C") (pinfunction "C_C") (pintype "passive"))
      (node (ref "R28") (pin "1") (pinfunction "1_1") (pintype "passive"))
      (node (ref "R30") (pin "1") (pinfunction "1_1") (pintype "passive"))
    )
    (net (code "29") (name "Net-(D5-PadC)") (class "Default")
      (node (ref "D5") (pin "C") (pinfunction "C_C") (pintype "passive"))
      (node (ref "D6") (pin "C") (pinfunction "C_C") (pintype "passive"))
      (node (ref "R36") (pin "2") (pinfunction "2_2") (pintype "passive"))
    )
    (net (code "30") (name "Net-(IC1-TACH1)") (class "Default")
      (node (ref "C8") (pin "1") (pinfunction "1_1") (pintype "passive"))
      (node (ref "IC1") (pin "7") (pinfunction "TACH1_7") (pintype "input"))
      (node (ref "R17") (pin "1") (pinfunction "1_1") (pintype "passive"))
    )
    (net (code "31") (name "Net-(IC1-TACH2)") (class "Default")
      (node (ref "C10") (pin "1") (pinfunction "1_1") (pintype "passive"))
      (node (ref "IC1") (pin "9") (pinfunction "TACH2_9") (pintype "input"))
      (node (ref "R21") (pin "1") (pinfunction "1_1") (pintype "passive"))
    )
    (net (code "32") (name "Net-(IC1-~{FF}{slash}~{FS})") (class "Default")
      (node (ref "IC1") (pin "12") (pinfunction "~{FF}/~{FS}_12") (pintype "bidirectional"))
      (node (ref "R20") (pin "1") (pinfunction "1_1") (pintype "passive"))
    )
    (net (code "33") (name "Net-(IC1-~{SHDN})") (class "Default")
      (node (ref "IC1") (pin "11") (pinfunction "~{SHDN}_11") (pintype "output"))
      (node (ref "R19") (pin "1") (pinfunction "1_1") (pintype "passive"))
    )
    (net (code "34") (name "Net-(IC2-BR)") (class "Default")
      (node (ref "IC2") (pin "8") (pinfunction "BR_8") (pintype "input"))
      (node (ref "R29") (pin "2") (pinfunction "2_2") (pintype "passive"))
      (node (ref "R38") (pin "1") (pinfunction "1_1") (pintype "passive"))
    )
    (net (code "35") (name "Net-(IC2-FB)") (class "Default")
      (node (ref "C25") (pin "2") (pinfunction "2_2") (pintype "passive"))
      (node (ref "C28") (pin "1") (pinfunction "1_1") (pintype "passive"))
      (node (ref "IC2") (pin "7") (pinfunction "FB_7") (pintype "input"))
      (node (ref "OK3") (pin "4") (pinfunction "COL_4") (pintype "passive"))
    )
    (net (code "36") (name "Net-(IC2-ZCD)") (class "Default")
      (node (ref "C26") (pin "1") (pinfunction "1_1") (pintype "passive"))
      (node (ref "IC2") (pin "6") (pinfunction "ZCD_6") (pintype "input"))
      (node (ref "R34") (pin "1") (pinfunction "1_1") (pintype "passive"))
      (node (ref "R36") (pin "1") (pinfunction "1_1") (pintype "passive"))
      (node (ref "R40") (pin "2") (pinfunction "2_2") (pintype "passive"))
    )
    (net (code "37") (name "Net-(IC3-C)") (class "Default")
      (node (ref "C27") (pin "1") (pinfunction "1_1") (pintype "passive"))
      (node (ref "IC3") (pin "1") (pinfunction "C_1") (pintype "passive"))
      (node (ref "OK3") (pin "2") (pinfunction "C_2") (pintype "passive"))
      (node (ref "R35") (pin "2") (pinfunction "2_2") (pintype "passive"))
    )
    (net (code "38") (name "Net-(IC3-REF)") (class "Default")
      (node (ref "C24") (pin "2") (pinfunction "2_2") (pintype "passive"))
      (node (ref "IC3") (pin "2") (pinfunction "REF_2") (pintype "passive"))
      (node (ref "R37") (pin "1") (pinfunction "1_1") (pintype "passive"))
      (node (ref "R39") (pin "2") (pinfunction "2_2") (pintype "passive"))
      (node (ref "R42") (pin "2") (pinfunction "2_2") (pintype "passive"))
    )
    (net (code "39") (name "Net-(JP2-PadCOM)") (class "Default")
      (node (ref "JP2") (pin "COM") (pinfunction "COM_COM") (pintype "passive"))
      (node (ref "R32") (pin "1") (pinfunction "1_1") (pintype "passive"))
    )
    (net (code "40") (name "Net-(L1-1)") (class "Default")
      (node (ref "B1") (pin "+") (pinfunction "+_+") (pintype "passive"))
      (node (ref "C12") (pin "+") (pinfunction "+_+") (pintype "passive"))
      (node (ref "L1") (pin "P$1") (pinfunction "1_P$1") (pintype "passive"))
    )
    (net (code "41") (name "Net-(L1-2)") (class "Default")
      (node (ref "C11") (pin "1") (pinfunction "1_1") (pintype "passive"))
      (node (ref "C13") (pin "+") (pinfunction "+_+") (pintype "passive"))
      (node (ref "L1") (pin "P$2") (pinfunction "2_P$2") (pintype "passive"))
      (node (ref "R22") (pin "1") (pinfunction "1_1") (pintype "passive"))
      (node (ref "R23") (pin "1") (pinfunction "1_1") (pintype "passive"))
      (node (ref "TR1") (pin "2") (pinfunction "P1_2") (pintype "passive"))
    )
    (net (code "42") (name "Net-(LED1-PadC)") (class "Default")
      (node (ref "LED1") (pin "C") (pinfunction "C_C") (pintype "passive"))
      (node (ref "R12") (pin "1") (pinfunction "1_1") (pintype "passive"))
    )
    (net (code "43") (name "Net-(NTC1-P$2)") (class "Default")
      (node (ref "NTC1") (pin "2") (pinfunction "P$2_2") (pintype "bidirectional"))
      (node (ref "Q1") (pin "A1") (pinfunction "A1_A1") (pintype "passive"))
      (node (ref "R1") (pin "1") (pinfunction "1_1") (pintype "passive"))
    )
    (net (code "44") (name "Net-(OK1-A1)") (class "Default")
      (node (ref "OK1") (pin "4") (pinfunction "A1_4") (pintype "passive"))
      (node (ref "R4") (pin "1") (pinfunction "1_1") (pintype "passive"))
    )
    (net (code "45") (name "Net-(OK1-A2)") (class "Default")
      (node (ref "OK1") (pin "6") (pinfunction "A2_6") (pintype "passive"))
      (node (ref "Q2") (pin "G") (pinfunction "G_G") (pintype "passive"))
      (node (ref "R3") (pin "1") (pinfunction "1_1") (pintype "passive"))
    )
    (net (code "46") (name "Net-(OK1-C)") (class "Default")
      (node (ref "OK1") (pin "2") (pinfunction "C_2") (pintype "passive"))
      (node (ref "R2") (pin "1") (pinfunction "1_1") (pintype "passive"))
    )
    (net (code "47") (name "Net-(OK2-A1)") (class "Default")
      (node (ref "OK2") (pin "4") (pinfunction "A1_4") (pintype "passive"))
      (node (ref "Q1") (pin "G") (pinfunction "G_G") (pintype "passive"))
      (node (ref "R1") (pin "2") (pinfunction "2_2") (pintype "passive"))
    )
    (net (code "48") (name "Net-(OK2-A2)") (class "Default")
      (node (ref "OK2") (pin "6") (pinfunction "A2_6") (pintype "passive"))
      (node (ref "R6") (pin "1") (pinfunction "1_1") (pintype "passive"))
    )
    (net (code "49") (name "Net-(OK2-C)") (class "Default")
      (node (ref "OK2") (pin "2") (pinfunction "C_2") (pintype "passive"))
      (node (ref "R7") (pin "1") (pinfunction "1_1") (pintype "passive"))
    )
    (net (code "50") (name "Net-(OK3-A)") (class "Default")
      (node (ref "OK3") (pin "1") (pinfunction "A_1") (pintype "passive"))
      (node (ref "R32") (pin "2") (pinfunction "2_2") (pintype "passive"))
      (node (ref "R35") (pin "1") (pinfunction "1_1") (pintype "passive"))
    )
    (net (code "51") (name "Net-(Q4-D)") (class "Default")
      (node (ref "Q4") (pin "3") (pinfunction "D_3") (pintype "passive"))
      (node (ref "R7") (pin "2") (pinfunction "2_2") (pintype "passive"))
    )
    (net (code "52") (name "Net-(Q5-D)") (class "Default")
      (node (ref "Q5") (pin "3") (pinfunction "D_3") (pintype "passive"))
      (node (ref "R12") (pin "2") (pinfunction "2_2") (pintype "passive"))
    )
    (net (code "53") (name "Net-(Q6-D)") (class "Default")
      (node (ref "C7") (pin "1") (pinfunction "1_1") (pintype "passive"))
      (node (ref "Q6") (pin "MB") (pinfunction "D_MB") (pintype "passive"))
      (node (ref "R11") (pin "1") (pinfunction "1_1") (pintype "passive"))
    )
    (net (code "54") (name "Net-(Q6-G)") (class "Default")
      (node (ref "C7") (pin "2") (pinfunction "2_2") (pintype "passive"))
      (node (ref "Q6") (pin "4") (pinfunction "G_4") (pintype "passive"))
      (node (ref "R18") (pin "2") (pinfunction "2_2") (pintype "passive"))
    )
    (net (code "55") (name "Net-(R22-Pad2)") (class "Default")
      (node (ref "R22") (pin "2") (pinfunction "2_2") (pintype "passive"))
      (node (ref "R24") (pin "2") (pinfunction "2_2") (pintype "passive"))
    )
    (net (code "56") (name "Net-(R23-Pad2)") (class "Default")
      (node (ref "R23") (pin "2") (pinfunction "2_2") (pintype "passive"))
      (node (ref "R26") (pin "1") (pinfunction "1_1") (pintype "passive"))
    )
    (net (code "57") (name "Net-(R26-Pad2)") (class "Default")
      (node (ref "R26") (pin "2") (pinfunction "2_2") (pintype "passive"))
      (node (ref "R29") (pin "1") (pinfunction "1_1") (pintype "passive"))
    )
    (net (code "58") (name "Net-(R33-Pad1)") (class "Default")
      (node (ref "R33") (pin "1") (pinfunction "1_1") (pintype "passive"))
      (node (ref "R37") (pin "2") (pinfunction "2_2") (pintype "passive"))
    )
    (net (code "59") (name "Net-(TR1-P1_DOT)") (class "Default")
      (node (ref "D2") (pin "A") (pinfunction "A_A") (pintype "passive"))
      (node (ref "IC2") (pin "13") (pinfunction "DRAIN_13") (pintype "output"))
      (node (ref "IC2") (pin "14") (pinfunction "DRAIN_14") (pintype "output"))
      (node (ref "IC2") (pin "15") (pinfunction "DRAIN_15") (pintype "output"))
      (node (ref "IC2") (pin "16") (pinfunction "DRAIN_16") (pintype "output"))
      (node (ref "TR1") (pin "4") (pinfunction "P1_DOT_4") (pintype "passive"))
    )
    (net (code "60") (name "Net-(VAR1-P$1)") (class "Default")
      (node (ref "SAR1") (pin "P$1") (pinfunction "P$1_P$1") (pintype "bidirectional"))
      (node (ref "VAR1") (pin "1") (pinfunction "P$1_1") (pintype "bidirectional"))
      (node (ref "VAR2") (pin "2") (pinfunction "P$2_2") (pintype "bidirectional"))
    )
    (net (code "61") (name "Net-(X4A-S)") (class "Default")
      (node (ref "C3") (pin "2") (pinfunction "2_2") (pintype "passive"))
      (node (ref "C5") (pin "2") (pinfunction "2_2") (pintype "passive"))
      (node (ref "R11") (pin "2") (pinfunction "2_2") (pintype "passive"))
      (node (ref "X4") (pin "1") (pinfunction "S_1") (pintype "passive"))
      (node (ref "X5") (pin "1") (pinfunction "S_1") (pintype "passive"))
    )
    (net (code "62") (name "PE") (class "Default")
      (node (ref "J1") (pin "PE") (pinfunction "PE_PE") (pintype "bidirectional"))
      (node (ref "J2") (pin "P$1") (pinfunction "P$1_P$1") (pintype "bidirectional"))
      (node (ref "J2") (pin "P$2") (pinfunction "P$1_P$2") (pintype "bidirectional"))
      (node (ref "J3") (pin "P$1") (pinfunction "P$1_P$1") (pintype "bidirectional"))
      (node (ref "J3") (pin "P$2") (pinfunction "P$1_P$2") (pintype "bidirectional"))
      (node (ref "J4") (pin "P$1") (pinfunction "P$1_P$1") (pintype "bidirectional"))
      (node (ref "J4") (pin "P$2") (pinfunction "P$1_P$2") (pintype "bidirectional"))
      (node (ref "J5") (pin "1") (pinfunction "1_1") (pintype "passive"))
      (node (ref "J5") (pin "NC1") (pinfunction "1_NC1") (pintype "passive"))
      (node (ref "J5") (pin "NC2") (pinfunction "1_NC2") (pintype "passive"))
      (node (ref "J5") (pin "NC3") (pinfunction "1_NC3") (pintype "passive"))
      (node (ref "J5") (pin "NC4") (pinfunction "1_NC4") (pintype "passive"))
      (node (ref "JP1") (pin "NC") (pinfunction "NC_NC") (pintype "passive"))
      (node (ref "SAR1") (pin "P$2") (pinfunction "P$2_P$2") (pintype "bidirectional"))
      (node (ref "SW1") (pin "PE1") (pinfunction "PE_PE1") (pintype "power_in"))
      (node (ref "SW1") (pin "PE2") (pinfunction "PE_PE2") (pintype "power_in"))
      (node (ref "X1") (pin "3") (pinfunction "1_3") (pintype "passive"))
      (node (ref "X1") (pin "6") (pinfunction "1_6") (pintype "passive"))
      (node (ref "X2") (pin "3") (pinfunction "1_3") (pintype "passive"))
      (node (ref "X3") (pin "1") (pinfunction "1_1") (pintype "passive"))
      (node (ref "X3") (pin "2") (pinfunction "1_2") (pintype "passive"))
      (node (ref "ZD1") (pin "C") (pinfunction "1_C") (pintype "passive"))
      (node (ref "ZD2") (pin "C") (pinfunction "1_C") (pintype "passive"))
    )
    (net (code "63") (name "PWM_OUT") (class "Default")
      (node (ref "IC1") (pin "6") (pinfunction "PWM_6") (pintype "output"))
      (node (ref "R15") (pin "2") (pinfunction "2_2") (pintype "passive"))
      (node (ref "R18") (pin "1") (pinfunction "1_1") (pintype "passive"))
      (node (ref "X4") (pin "4") (pinfunction "S_4") (pintype "passive"))
      (node (ref "X5") (pin "4") (pinfunction "S_4") (pintype "passive"))
    )
    (net (code "64") (name "PWR_DIRECT") (class "Default")
      (node (ref "Q3") (pin "1") (pinfunction "G_1") (pintype "passive"))
      (node (ref "R5") (pin "2") (pinfunction "2_2") (pintype "passive"))
      (node (ref "X3") (pin "12") (pinfunction "1_12") (pintype "passive"))
    )
    (net (code "65") (name "PWR_DIR_OUT") (class "Default")
      (node (ref "Q3") (pin "3") (pinfunction "D_3") (pintype "passive"))
      (node (ref "Q5") (pin "1") (pinfunction "G_1") (pintype "passive"))
      (node (ref "R16") (pin "2") (pinfunction "2_2") (pintype "passive"))
      (node (ref "R2") (pin "2") (pinfunction "2_2") (pintype "passive"))
    )
    (net (code "66") (name "PWR_SSTART") (class "Default")
      (node (ref "Q4") (pin "1") (pinfunction "G_1") (pintype "passive"))
      (node (ref "R10") (pin "2") (pinfunction "2_2") (pintype "passive"))
      (node (ref "X3") (pin "11") (pinfunction "1_11") (pintype "passive"))
    )
    (net (code "67") (name "SSCL") (class "Default")
      (node (ref "IC1") (pin "15") (pinfunction "SCL_15") (pintype "input"))
      (node (ref "X3") (pin "13") (pinfunction "1_13") (pintype "passive"))
    )
    (net (code "68") (name "SSDA") (class "Default")
      (node (ref "IC1") (pin "14") (pinfunction "SDA_14") (pintype "bidirectional"))
      (node (ref "X3") (pin "14") (pinfunction "1_14") (pintype "passive"))
    )
    (net (code "69") (name "TEMP1_N") (class "Default")
      (node (ref "C9") (pin "2") (pinfunction "2_2") (pintype "passive"))
      (node (ref "IC1") (pin "2") (pinfunction "DXN_2") (pintype "bidirectional"))
      (node (ref "X6") (pin "2") (pinfunction "S_2") (pintype "passive"))
    )
    (net (code "70") (name "TEMP1_P") (class "Default")
      (node (ref "C9") (pin "1") (pinfunction "1_1") (pintype "passive"))
      (node (ref "IC1") (pin "1") (pinfunction "DXP_1") (pintype "input"))
      (node (ref "X6") (pin "1") (pinfunction "S_1") (pintype "passive"))
    )
    (net (code "71") (name "unconnected-(KK1-K-PadA2,5)") (class "Default")
      (node (ref "KK1") (pin "A2,5") (pinfunction "K_A2,5") (pintype "passive"))
    )
    (net (code "72") (name "unconnected-(KK1-K-PadB2,5)") (class "Default")
      (node (ref "KK1") (pin "B2,5") (pinfunction "K_B2,5") (pintype "passive"))
    )
    (net (code "73") (name "unconnected-(TR1-P1_MIDDLE-Pad3)") (class "Default")
      (node (ref "TR1") (pin "3") (pinfunction "P1_MIDDLE_3") (pintype "passive"))
    )
  )
)
